# PC_Memory.net
KiCad netlist of a schematic drawn in Altium Designer
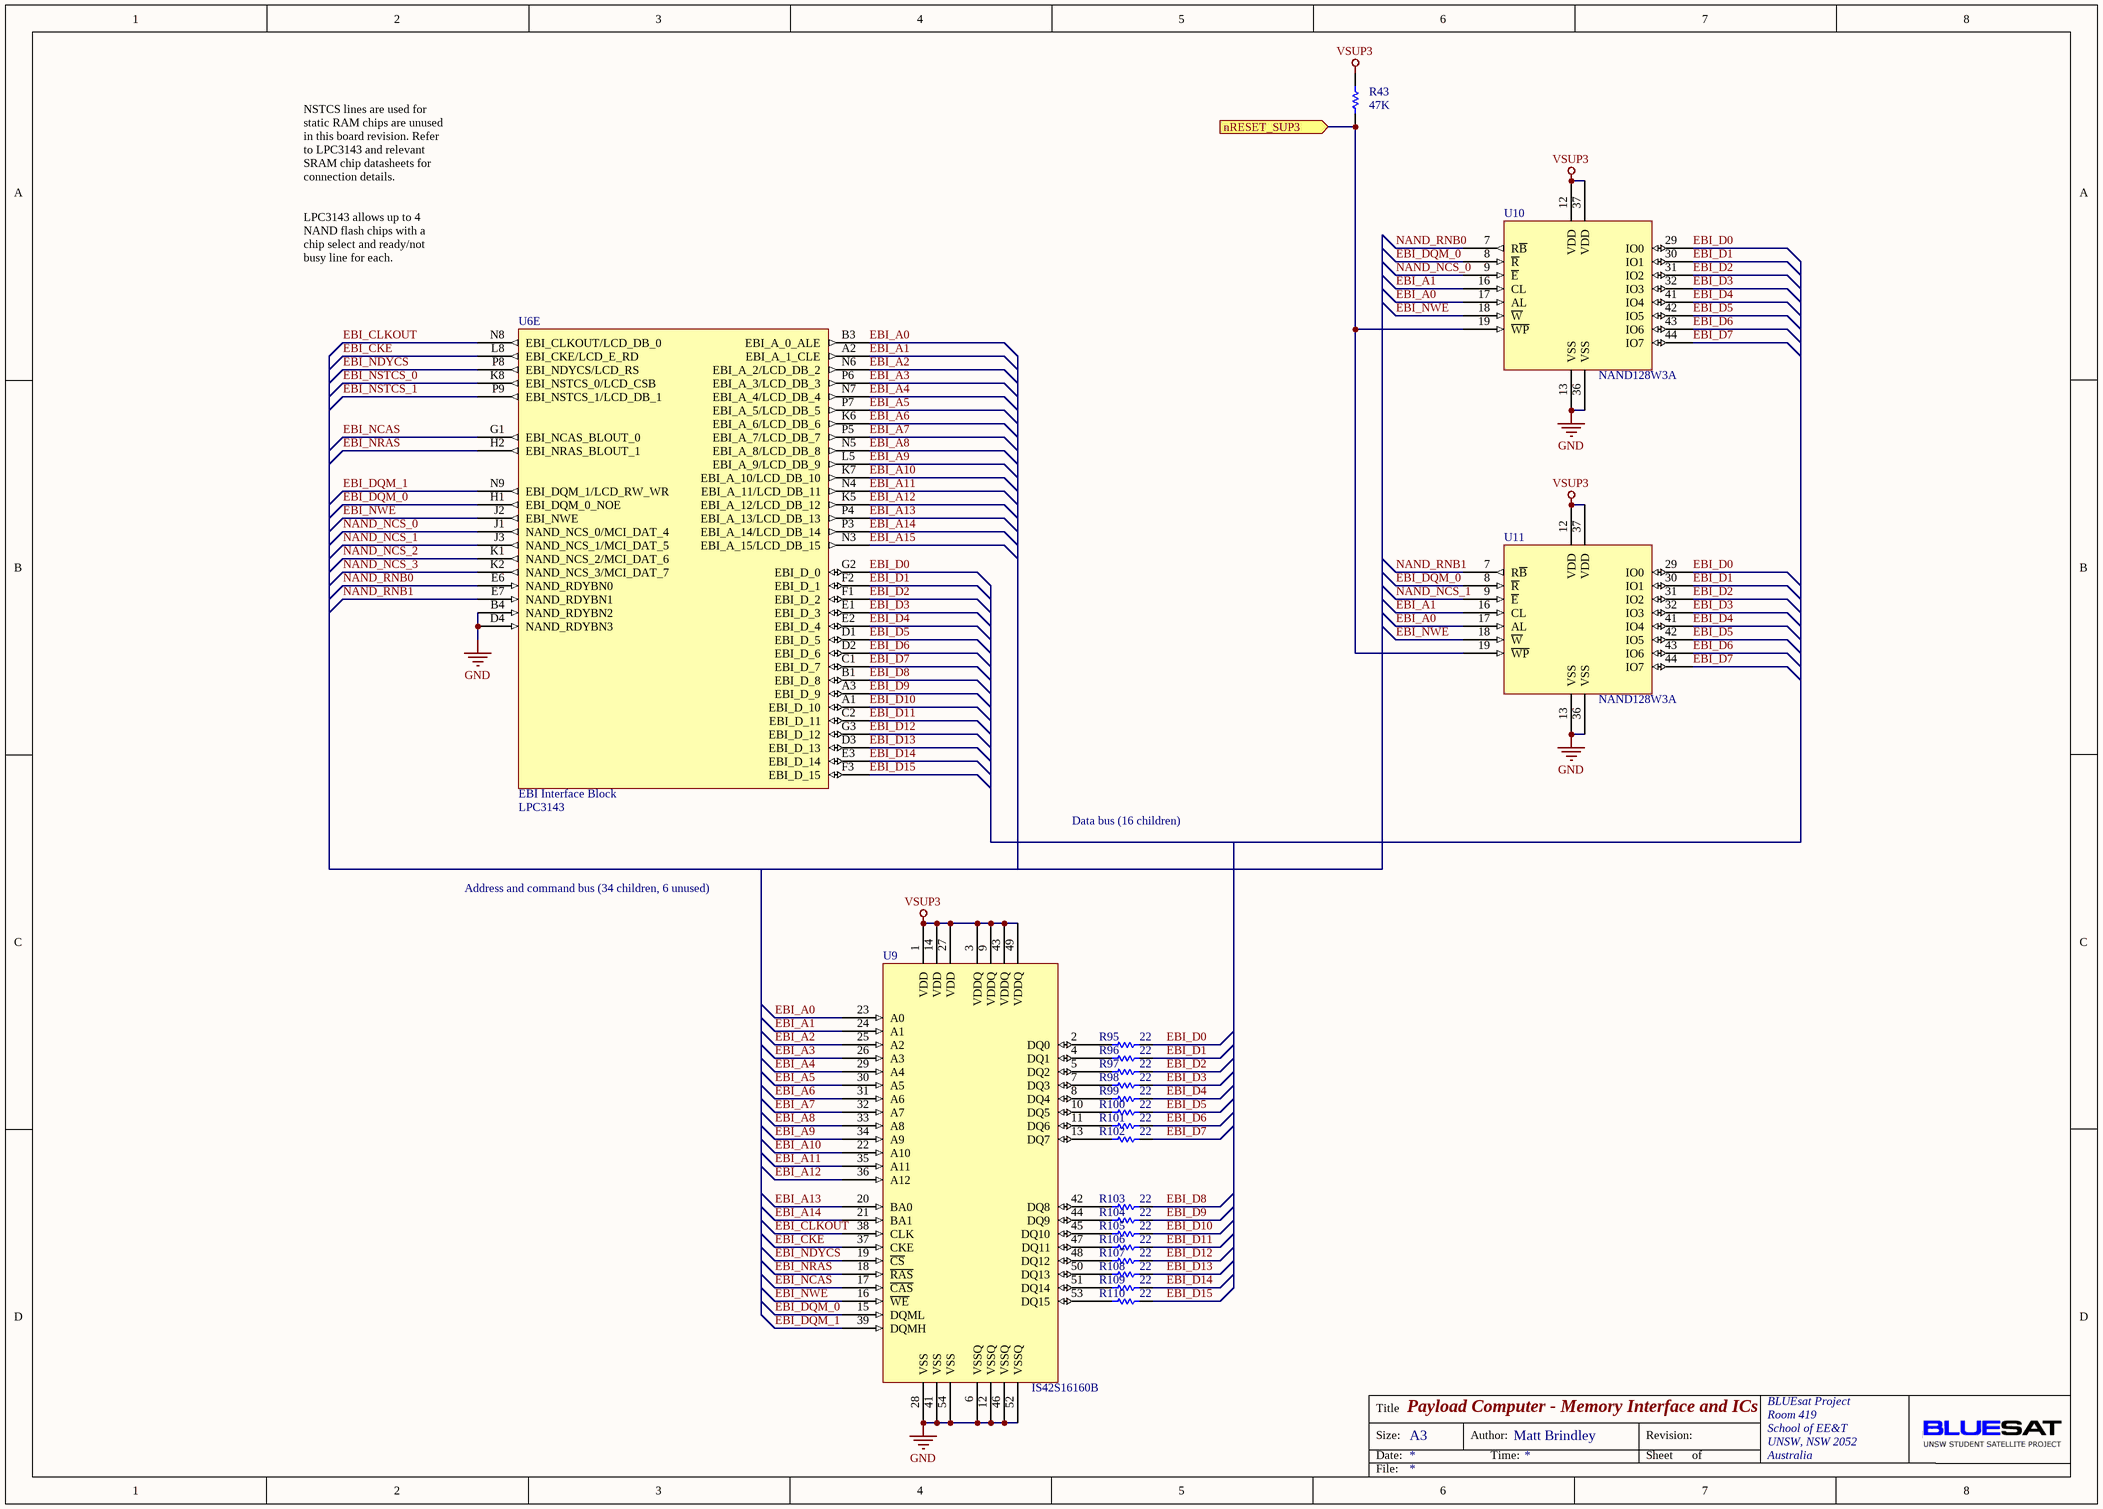
[diagram p0: PC_Memory.SchDoc]

(export (version "E")
  (design (tool "Eeschema 10.0.6"))
  (components
    (comp (ref "R43")
      (value "47K")
      (footprint "6-0805_L")
      (description "Semiconductor Resistor")
      (fields (field (name "Comment") "Res Semi") (field (name "PUBLISHER") "Altium Limited"))
      (libsource (lib "Miscellaneous Devices") (part "Res Semi"))
    )
    (comp (ref "R95")
      (value "22")
      (footprint "6-0805_L")
      (description "Semiconductor Resistor")
      (fields (field (name "Comment") "Res Semi") (field (name "PUBLISHER") "Altium Limited"))
      (libsource (lib "Miscellaneous Devices") (part "Res Semi"))
    )
    (comp (ref "R96")
      (value "22")
      (footprint "6-0805_L")
      (description "Semiconductor Resistor")
      (fields (field (name "Comment") "Res Semi") (field (name "PUBLISHER") "Altium Limited"))
      (libsource (lib "Miscellaneous Devices") (part "Res Semi"))
    )
    (comp (ref "R97")
      (value "22")
      (footprint "6-0805_L")
      (description "Semiconductor Resistor")
      (fields (field (name "Comment") "Res Semi") (field (name "PUBLISHER") "Altium Limited"))
      (libsource (lib "Miscellaneous Devices") (part "Res Semi"))
    )
    (comp (ref "R98")
      (value "22")
      (footprint "6-0805_L")
      (description "Semiconductor Resistor")
      (fields (field (name "Comment") "Res Semi") (field (name "PUBLISHER") "Altium Limited"))
      (libsource (lib "Miscellaneous Devices") (part "Res Semi"))
    )
    (comp (ref "R99")
      (value "22")
      (footprint "6-0805_L")
      (description "Semiconductor Resistor")
      (fields (field (name "Comment") "Res Semi") (field (name "PUBLISHER") "Altium Limited"))
      (libsource (lib "Miscellaneous Devices") (part "Res Semi"))
    )
    (comp (ref "R100")
      (value "22")
      (footprint "6-0805_L")
      (description "Semiconductor Resistor")
      (fields (field (name "Comment") "Res Semi") (field (name "PUBLISHER") "Altium Limited"))
      (libsource (lib "Miscellaneous Devices") (part "Res Semi"))
    )
    (comp (ref "R101")
      (value "22")
      (footprint "6-0805_L")
      (description "Semiconductor Resistor")
      (fields (field (name "Comment") "Res Semi") (field (name "PUBLISHER") "Altium Limited"))
      (libsource (lib "Miscellaneous Devices") (part "Res Semi"))
    )
    (comp (ref "R102")
      (value "22")
      (footprint "6-0805_L")
      (description "Semiconductor Resistor")
      (fields (field (name "Comment") "Res Semi") (field (name "PUBLISHER") "Altium Limited"))
      (libsource (lib "Miscellaneous Devices") (part "Res Semi"))
    )
    (comp (ref "R103")
      (value "22")
      (footprint "6-0805_L")
      (description "Semiconductor Resistor")
      (fields (field (name "Comment") "Res Semi") (field (name "PUBLISHER") "Altium Limited"))
      (libsource (lib "Miscellaneous Devices") (part "Res Semi"))
    )
    (comp (ref "R104")
      (value "22")
      (footprint "6-0805_L")
      (description "Semiconductor Resistor")
      (fields (field (name "Comment") "Res Semi") (field (name "PUBLISHER") "Altium Limited"))
      (libsource (lib "Miscellaneous Devices") (part "Res Semi"))
    )
    (comp (ref "R105")
      (value "22")
      (footprint "6-0805_L")
      (description "Semiconductor Resistor")
      (fields (field (name "Comment") "Res Semi") (field (name "PUBLISHER") "Altium Limited"))
      (libsource (lib "Miscellaneous Devices") (part "Res Semi"))
    )
    (comp (ref "R106")
      (value "22")
      (footprint "6-0805_L")
      (description "Semiconductor Resistor")
      (fields (field (name "Comment") "Res Semi") (field (name "PUBLISHER") "Altium Limited"))
      (libsource (lib "Miscellaneous Devices") (part "Res Semi"))
    )
    (comp (ref "R107")
      (value "22")
      (footprint "6-0805_L")
      (description "Semiconductor Resistor")
      (fields (field (name "Comment") "Res Semi") (field (name "PUBLISHER") "Altium Limited"))
      (libsource (lib "Miscellaneous Devices") (part "Res Semi"))
    )
    (comp (ref "R108")
      (value "22")
      (footprint "6-0805_L")
      (description "Semiconductor Resistor")
      (fields (field (name "Comment") "Res Semi") (field (name "PUBLISHER") "Altium Limited"))
      (libsource (lib "Miscellaneous Devices") (part "Res Semi"))
    )
    (comp (ref "R109")
      (value "22")
      (footprint "6-0805_L")
      (description "Semiconductor Resistor")
      (fields (field (name "Comment") "Res Semi") (field (name "PUBLISHER") "Altium Limited"))
      (libsource (lib "Miscellaneous Devices") (part "Res Semi"))
    )
    (comp (ref "R110")
      (value "22")
      (footprint "6-0805_L")
      (description "Semiconductor Resistor")
      (fields (field (name "Comment") "Res Semi") (field (name "PUBLISHER") "Altium Limited"))
      (libsource (lib "Miscellaneous Devices") (part "Res Semi"))
    )
    (comp (ref "U6")
      (value "LPC3143")
      (footprint "PC_Footprints:BGA180C80P14X14_1200X1200X120")
      (description "NXP ARM9 based microcontroller")
      (fields (field (name "PUBLISHER") "BLUEsat Project"))
      (libsource (lib "PC_Components") (part "LPC3143"))
    )
    (comp (ref "U9")
      (value "IS42S16160B")
      (footprint "TSOP80P1180X120-54M")
      (description "16Mb x 16 (256Mb) Parallel Interface SDRAM")
      (fields (field (name "PUBLISHER") "Altium Limited"))
      (libsource (lib "PC_Components") (part "IS42S16160B"))
    )
    (comp (ref "U10")
      (value "NAND128W3A")
      (footprint "TSSOP50P2000X120-48M")
      (description "128Mb 8b wide NAND Flash")
      (fields (field (name "PUBLISHER") "Altium Limited"))
      (libsource (lib "PC_Components") (part "NAND128W3A"))
    )
    (comp (ref "U11")
      (value "NAND128W3A")
      (footprint "TSSOP50P2000X120-48M")
      (description "128Mb 8b wide NAND Flash")
      (fields (field (name "PUBLISHER") "Altium Limited"))
      (libsource (lib "PC_Components") (part "NAND128W3A"))
    )
  )
  (nets
    (net (code "1") (name "/EBI_A0") (class "Default")
      (node (ref "U10") (pin "17") (pinfunction "AL_17") (pintype "input"))
      (node (ref "U11") (pin "17") (pinfunction "AL_17") (pintype "input"))
      (node (ref "U6") (pin "B3") (pinfunction "EBI_A_0_ALE_B3") (pintype "output"))
      (node (ref "U9") (pin "23") (pinfunction "A0_23") (pintype "input"))
    )
    (net (code "2") (name "/EBI_A1") (class "Default")
      (node (ref "U10") (pin "16") (pinfunction "CL_16") (pintype "input"))
      (node (ref "U11") (pin "16") (pinfunction "CL_16") (pintype "input"))
      (node (ref "U6") (pin "A2") (pinfunction "EBI_A_1_CLE_A2") (pintype "output"))
      (node (ref "U9") (pin "24") (pinfunction "A1_24") (pintype "input"))
    )
    (net (code "3") (name "/EBI_A2") (class "Default")
      (node (ref "U6") (pin "N6") (pinfunction "EBI_A_2/LCD_DB_2_N6") (pintype "output"))
      (node (ref "U9") (pin "25") (pinfunction "A2_25") (pintype "input"))
    )
    (net (code "4") (name "/EBI_A3") (class "Default")
      (node (ref "U6") (pin "P6") (pinfunction "EBI_A_3/LCD_DB_3_P6") (pintype "output"))
      (node (ref "U9") (pin "26") (pinfunction "A3_26") (pintype "input"))
    )
    (net (code "5") (name "/EBI_A4") (class "Default")
      (node (ref "U6") (pin "N7") (pinfunction "EBI_A_4/LCD_DB_4_N7") (pintype "output"))
      (node (ref "U9") (pin "29") (pinfunction "A4_29") (pintype "input"))
    )
    (net (code "6") (name "/EBI_A5") (class "Default")
      (node (ref "U6") (pin "P7") (pinfunction "EBI_A_5/LCD_DB_5_P7") (pintype "output"))
      (node (ref "U9") (pin "30") (pinfunction "A5_30") (pintype "input"))
    )
    (net (code "7") (name "/EBI_A6") (class "Default")
      (node (ref "U6") (pin "K6") (pinfunction "EBI_A_6/LCD_DB_6_K6") (pintype "output"))
      (node (ref "U9") (pin "31") (pinfunction "A6_31") (pintype "input"))
    )
    (net (code "8") (name "/EBI_A7") (class "Default")
      (node (ref "U6") (pin "P5") (pinfunction "EBI_A_7/LCD_DB_7_P5") (pintype "output"))
      (node (ref "U9") (pin "32") (pinfunction "A7_32") (pintype "input"))
    )
    (net (code "9") (name "/EBI_A8") (class "Default")
      (node (ref "U6") (pin "N5") (pinfunction "EBI_A_8/LCD_DB_8_N5") (pintype "output"))
      (node (ref "U9") (pin "33") (pinfunction "A8_33") (pintype "input"))
    )
    (net (code "10") (name "/EBI_A9") (class "Default")
      (node (ref "U6") (pin "L5") (pinfunction "EBI_A_9/LCD_DB_9_L5") (pintype "output"))
      (node (ref "U9") (pin "34") (pinfunction "A9_34") (pintype "input"))
    )
    (net (code "11") (name "/EBI_A10") (class "Default")
      (node (ref "U6") (pin "K7") (pinfunction "EBI_A_10/LCD_DB_10_K7") (pintype "output"))
      (node (ref "U9") (pin "22") (pinfunction "A10_22") (pintype "input"))
    )
    (net (code "12") (name "/EBI_A11") (class "Default")
      (node (ref "U6") (pin "N4") (pinfunction "EBI_A_11/LCD_DB_11_N4") (pintype "output"))
      (node (ref "U9") (pin "35") (pinfunction "A11_35") (pintype "input"))
    )
    (net (code "13") (name "/EBI_A12") (class "Default")
      (node (ref "U6") (pin "K5") (pinfunction "EBI_A_12/LCD_DB_12_K5") (pintype "output"))
      (node (ref "U9") (pin "36") (pinfunction "A12_36") (pintype "input"))
    )
    (net (code "14") (name "/EBI_A13") (class "Default")
      (node (ref "U6") (pin "P4") (pinfunction "EBI_A_13/LCD_DB_13_P4") (pintype "output"))
      (node (ref "U9") (pin "20") (pinfunction "BA0_20") (pintype "input"))
    )
    (net (code "15") (name "/EBI_A14") (class "Default")
      (node (ref "U6") (pin "P3") (pinfunction "EBI_A_14/LCD_DB_14_P3") (pintype "output"))
      (node (ref "U9") (pin "21") (pinfunction "BA1_21") (pintype "input"))
    )
    (net (code "16") (name "/EBI_A15") (class "Default")
      (node (ref "U6") (pin "N3") (pinfunction "EBI_A_15/LCD_DB_15_N3") (pintype "output"))
    )
    (net (code "17") (name "/EBI_CKE") (class "Default")
      (node (ref "U6") (pin "L8") (pinfunction "EBI_CKE/LCD_E_RD_L8") (pintype "output"))
      (node (ref "U9") (pin "37") (pinfunction "CKE_37") (pintype "input"))
    )
    (net (code "18") (name "/EBI_CLKOUT") (class "Default")
      (node (ref "U6") (pin "N8") (pinfunction "EBI_CLKOUT/LCD_DB_0_N8") (pintype "output"))
      (node (ref "U9") (pin "38") (pinfunction "CLK_38") (pintype "input"))
    )
    (net (code "19") (name "/EBI_D0") (class "Default")
      (node (ref "R95") (pin "2") (pinfunction "2_2") (pintype "passive"))
      (node (ref "U10") (pin "29") (pinfunction "IO0_29") (pintype "bidirectional"))
      (node (ref "U11") (pin "29") (pinfunction "IO0_29") (pintype "bidirectional"))
      (node (ref "U6") (pin "G2") (pinfunction "EBI_D_0_G2") (pintype "bidirectional"))
    )
    (net (code "20") (name "/EBI_D1") (class "Default")
      (node (ref "R96") (pin "2") (pinfunction "2_2") (pintype "passive"))
      (node (ref "U10") (pin "30") (pinfunction "IO1_30") (pintype "bidirectional"))
      (node (ref "U11") (pin "30") (pinfunction "IO1_30") (pintype "bidirectional"))
      (node (ref "U6") (pin "F2") (pinfunction "EBI_D_1_F2") (pintype "bidirectional"))
    )
    (net (code "21") (name "/EBI_D2") (class "Default")
      (node (ref "R97") (pin "2") (pinfunction "2_2") (pintype "passive"))
      (node (ref "U10") (pin "31") (pinfunction "IO2_31") (pintype "bidirectional"))
      (node (ref "U11") (pin "31") (pinfunction "IO2_31") (pintype "bidirectional"))
      (node (ref "U6") (pin "F1") (pinfunction "EBI_D_2_F1") (pintype "bidirectional"))
    )
    (net (code "22") (name "/EBI_D3") (class "Default")
      (node (ref "R98") (pin "2") (pinfunction "2_2") (pintype "passive"))
      (node (ref "U10") (pin "32") (pinfunction "IO3_32") (pintype "bidirectional"))
      (node (ref "U11") (pin "32") (pinfunction "IO3_32") (pintype "bidirectional"))
      (node (ref "U6") (pin "E1") (pinfunction "EBI_D_3_E1") (pintype "bidirectional"))
    )
    (net (code "23") (name "/EBI_D4") (class "Default")
      (node (ref "R99") (pin "2") (pinfunction "2_2") (pintype "passive"))
      (node (ref "U10") (pin "41") (pinfunction "IO4_41") (pintype "bidirectional"))
      (node (ref "U11") (pin "41") (pinfunction "IO4_41") (pintype "bidirectional"))
      (node (ref "U6") (pin "E2") (pinfunction "EBI_D_4_E2") (pintype "bidirectional"))
    )
    (net (code "24") (name "/EBI_D5") (class "Default")
      (node (ref "R100") (pin "2") (pinfunction "2_2") (pintype "passive"))
      (node (ref "U10") (pin "42") (pinfunction "IO5_42") (pintype "bidirectional"))
      (node (ref "U11") (pin "42") (pinfunction "IO5_42") (pintype "bidirectional"))
      (node (ref "U6") (pin "D1") (pinfunction "EBI_D_5_D1") (pintype "bidirectional"))
    )
    (net (code "25") (name "/EBI_D6") (class "Default")
      (node (ref "R101") (pin "2") (pinfunction "2_2") (pintype "passive"))
      (node (ref "U10") (pin "43") (pinfunction "IO6_43") (pintype "bidirectional"))
      (node (ref "U11") (pin "43") (pinfunction "IO6_43") (pintype "bidirectional"))
      (node (ref "U6") (pin "D2") (pinfunction "EBI_D_6_D2") (pintype "bidirectional"))
    )
    (net (code "26") (name "/EBI_D7") (class "Default")
      (node (ref "R102") (pin "2") (pinfunction "2_2") (pintype "passive"))
      (node (ref "U10") (pin "44") (pinfunction "IO7_44") (pintype "bidirectional"))
      (node (ref "U11") (pin "44") (pinfunction "IO7_44") (pintype "bidirectional"))
      (node (ref "U6") (pin "C1") (pinfunction "EBI_D_7_C1") (pintype "bidirectional"))
    )
    (net (code "27") (name "/EBI_D8") (class "Default")
      (node (ref "R103") (pin "2") (pinfunction "2_2") (pintype "passive"))
      (node (ref "U6") (pin "B1") (pinfunction "EBI_D_8_B1") (pintype "bidirectional"))
    )
    (net (code "28") (name "/EBI_D9") (class "Default")
      (node (ref "R104") (pin "2") (pinfunction "2_2") (pintype "passive"))
      (node (ref "U6") (pin "A3") (pinfunction "EBI_D_9_A3") (pintype "bidirectional"))
    )
    (net (code "29") (name "/EBI_D10") (class "Default")
      (node (ref "R105") (pin "2") (pinfunction "2_2") (pintype "passive"))
      (node (ref "U6") (pin "A1") (pinfunction "EBI_D_10_A1") (pintype "bidirectional"))
    )
    (net (code "30") (name "/EBI_D11") (class "Default")
      (node (ref "R106") (pin "2") (pinfunction "2_2") (pintype "passive"))
      (node (ref "U6") (pin "C2") (pinfunction "EBI_D_11_C2") (pintype "bidirectional"))
    )
    (net (code "31") (name "/EBI_D12") (class "Default")
      (node (ref "R107") (pin "2") (pinfunction "2_2") (pintype "passive"))
      (node (ref "U6") (pin "G3") (pinfunction "EBI_D_12_G3") (pintype "bidirectional"))
    )
    (net (code "32") (name "/EBI_D13") (class "Default")
      (node (ref "R108") (pin "2") (pinfunction "2_2") (pintype "passive"))
      (node (ref "U6") (pin "D3") (pinfunction "EBI_D_13_D3") (pintype "bidirectional"))
    )
    (net (code "33") (name "/EBI_D14") (class "Default")
      (node (ref "R109") (pin "2") (pinfunction "2_2") (pintype "passive"))
      (node (ref "U6") (pin "E3") (pinfunction "EBI_D_14_E3") (pintype "bidirectional"))
    )
    (net (code "34") (name "/EBI_D15") (class "Default")
      (node (ref "R110") (pin "2") (pinfunction "2_2") (pintype "passive"))
      (node (ref "U6") (pin "F3") (pinfunction "EBI_D_15_F3") (pintype "bidirectional"))
    )
    (net (code "35") (name "/EBI_DQM_0") (class "Default")
      (node (ref "U10") (pin "8") (pinfunction "~{R}_8") (pintype "input"))
      (node (ref "U11") (pin "8") (pinfunction "~{R}_8") (pintype "input"))
      (node (ref "U6") (pin "H1") (pinfunction "EBI_DQM_0_NOE_H1") (pintype "output"))
      (node (ref "U9") (pin "15") (pinfunction "DQML_15") (pintype "input"))
    )
    (net (code "36") (name "/EBI_DQM_1") (class "Default")
      (node (ref "U6") (pin "N9") (pinfunction "EBI_DQM_1/LCD_RW_WR_N9") (pintype "output"))
      (node (ref "U9") (pin "39") (pinfunction "DQMH_39") (pintype "input"))
    )
    (net (code "37") (name "/EBI_NCAS") (class "Default")
      (node (ref "U6") (pin "G1") (pinfunction "EBI_NCAS_BLOUT_0_G1") (pintype "output"))
      (node (ref "U9") (pin "17") (pinfunction "~{CAS}_17") (pintype "input"))
    )
    (net (code "38") (name "/EBI_NDYCS") (class "Default")
      (node (ref "U6") (pin "P8") (pinfunction "EBI_NDYCS/LCD_RS_P8") (pintype "output"))
      (node (ref "U9") (pin "19") (pinfunction "~{CS}_19") (pintype "input"))
    )
    (net (code "39") (name "/EBI_NRAS") (class "Default")
      (node (ref "U6") (pin "H2") (pinfunction "EBI_NRAS_BLOUT_1_H2") (pintype "output"))
      (node (ref "U9") (pin "18") (pinfunction "~{RAS}_18") (pintype "input"))
    )
    (net (code "40") (name "/EBI_NSTCS_0") (class "Default")
      (node (ref "U6") (pin "K8") (pinfunction "EBI_NSTCS_0/LCD_CSB_K8") (pintype "output"))
    )
    (net (code "41") (name "/EBI_NSTCS_1") (class "Default")
      (node (ref "U6") (pin "P9") (pinfunction "EBI_NSTCS_1/LCD_DB_1_P9") (pintype "output"))
    )
    (net (code "42") (name "/EBI_NWE") (class "Default")
      (node (ref "U10") (pin "18") (pinfunction "~{W}_18") (pintype "input"))
      (node (ref "U11") (pin "18") (pinfunction "~{W}_18") (pintype "input"))
      (node (ref "U6") (pin "J2") (pinfunction "EBI_NWE_J2") (pintype "output"))
      (node (ref "U9") (pin "16") (pinfunction "~{WE}_16") (pintype "input"))
    )
    (net (code "43") (name "/NAND_NCS_0") (class "Default")
      (node (ref "U10") (pin "9") (pinfunction "~{E}_9") (pintype "input"))
      (node (ref "U6") (pin "J1") (pinfunction "NAND_NCS_0/MCI_DAT_4_J1") (pintype "output"))
    )
    (net (code "44") (name "/NAND_NCS_1") (class "Default")
      (node (ref "U11") (pin "9") (pinfunction "~{E}_9") (pintype "input"))
      (node (ref "U6") (pin "J3") (pinfunction "NAND_NCS_1/MCI_DAT_5_J3") (pintype "output"))
    )
    (net (code "45") (name "/NAND_NCS_2") (class "Default")
      (node (ref "U6") (pin "K1") (pinfunction "NAND_NCS_2/MCI_DAT_6_K1") (pintype "output"))
    )
    (net (code "46") (name "/NAND_NCS_3") (class "Default")
      (node (ref "U6") (pin "K2") (pinfunction "NAND_NCS_3/MCI_DAT_7_K2") (pintype "output"))
    )
    (net (code "47") (name "/NAND_RNB0") (class "Default")
      (node (ref "U10") (pin "7") (pinfunction "R~{B}_7") (pintype "output"))
      (node (ref "U6") (pin "E6") (pinfunction "NAND_RDYBN0_E6") (pintype "input"))
    )
    (net (code "48") (name "/NAND_RNB1") (class "Default")
      (node (ref "U11") (pin "7") (pinfunction "R~{B}_7") (pintype "output"))
      (node (ref "U6") (pin "E7") (pinfunction "NAND_RDYBN1_E7") (pintype "input"))
    )
    (net (code "49") (name "/nRESET_SUP3") (class "Default")
      (node (ref "R43") (pin "1") (pinfunction "1_1") (pintype "passive"))
      (node (ref "U10") (pin "19") (pinfunction "~{WP}_19") (pintype "input"))
      (node (ref "U11") (pin "19") (pinfunction "~{WP}_19") (pintype "input"))
    )
    (net (code "50") (name "GND") (class "Default")
      (node (ref "U10") (pin "13") (pinfunction "VSS_13") (pintype "power_in"))
      (node (ref "U10") (pin "36") (pinfunction "VSS_36") (pintype "power_in"))
      (node (ref "U11") (pin "13") (pinfunction "VSS_13") (pintype "power_in"))
      (node (ref "U11") (pin "36") (pinfunction "VSS_36") (pintype "power_in"))
      (node (ref "U6") (pin "B4") (pinfunction "NAND_RDYBN2_B4") (pintype "input"))
      (node (ref "U6") (pin "D4") (pinfunction "NAND_RDYBN3_D4") (pintype "input"))
      (node (ref "U9") (pin "12") (pinfunction "VSSQ_12") (pintype "power_in"))
      (node (ref "U9") (pin "28") (pinfunction "VSS_28") (pintype "power_in"))
      (node (ref "U9") (pin "41") (pinfunction "VSS_41") (pintype "power_in"))
      (node (ref "U9") (pin "46") (pinfunction "VSSQ_46") (pintype "power_in"))
      (node (ref "U9") (pin "52") (pinfunction "VSSQ_52") (pintype "power_in"))
      (node (ref "U9") (pin "54") (pinfunction "VSS_54") (pintype "power_in"))
      (node (ref "U9") (pin "6") (pinfunction "VSSQ_6") (pintype "power_in"))
    )
    (net (code "51") (name "Net-(U9-DQ0)") (class "Default")
      (node (ref "R95") (pin "1") (pinfunction "1_1") (pintype "passive"))
      (node (ref "U9") (pin "2") (pinfunction "DQ0_2") (pintype "bidirectional"))
    )
    (net (code "52") (name "Net-(U9-DQ1)") (class "Default")
      (node (ref "R96") (pin "1") (pinfunction "1_1") (pintype "passive"))
      (node (ref "U9") (pin "4") (pinfunction "DQ1_4") (pintype "bidirectional"))
    )
    (net (code "53") (name "Net-(U9-DQ2)") (class "Default")
      (node (ref "R97") (pin "1") (pinfunction "1_1") (pintype "passive"))
      (node (ref "U9") (pin "5") (pinfunction "DQ2_5") (pintype "bidirectional"))
    )
    (net (code "54") (name "Net-(U9-DQ3)") (class "Default")
      (node (ref "R98") (pin "1") (pinfunction "1_1") (pintype "passive"))
      (node (ref "U9") (pin "7") (pinfunction "DQ3_7") (pintype "bidirectional"))
    )
    (net (code "55") (name "Net-(U9-DQ4)") (class "Default")
      (node (ref "R99") (pin "1") (pinfunction "1_1") (pintype "passive"))
      (node (ref "U9") (pin "8") (pinfunction "DQ4_8") (pintype "bidirectional"))
    )
    (net (code "56") (name "Net-(U9-DQ5)") (class "Default")
      (node (ref "R100") (pin "1") (pinfunction "1_1") (pintype "passive"))
      (node (ref "U9") (pin "10") (pinfunction "DQ5_10") (pintype "bidirectional"))
    )
    (net (code "57") (name "Net-(U9-DQ6)") (class "Default")
      (node (ref "R101") (pin "1") (pinfunction "1_1") (pintype "passive"))
      (node (ref "U9") (pin "11") (pinfunction "DQ6_11") (pintype "bidirectional"))
    )
    (net (code "58") (name "Net-(U9-DQ7)") (class "Default")
      (node (ref "R102") (pin "1") (pinfunction "1_1") (pintype "passive"))
      (node (ref "U9") (pin "13") (pinfunction "DQ7_13") (pintype "bidirectional"))
    )
    (net (code "59") (name "Net-(U9-DQ8)") (class "Default")
      (node (ref "R103") (pin "1") (pinfunction "1_1") (pintype "passive"))
      (node (ref "U9") (pin "42") (pinfunction "DQ8_42") (pintype "bidirectional"))
    )
    (net (code "60") (name "Net-(U9-DQ9)") (class "Default")
      (node (ref "R104") (pin "1") (pinfunction "1_1") (pintype "passive"))
      (node (ref "U9") (pin "44") (pinfunction "DQ9_44") (pintype "bidirectional"))
    )
    (net (code "61") (name "Net-(U9-DQ10)") (class "Default")
      (node (ref "R105") (pin "1") (pinfunction "1_1") (pintype "passive"))
      (node (ref "U9") (pin "45") (pinfunction "DQ10_45") (pintype "bidirectional"))
    )
    (net (code "62") (name "Net-(U9-DQ11)") (class "Default")
      (node (ref "R106") (pin "1") (pinfunction "1_1") (pintype "passive"))
      (node (ref "U9") (pin "47") (pinfunction "DQ11_47") (pintype "bidirectional"))
    )
    (net (code "63") (name "Net-(U9-DQ12)") (class "Default")
      (node (ref "R107") (pin "1") (pinfunction "1_1") (pintype "passive"))
      (node (ref "U9") (pin "48") (pinfunction "DQ12_48") (pintype "bidirectional"))
    )
    (net (code "64") (name "Net-(U9-DQ13)") (class "Default")
      (node (ref "R108") (pin "1") (pinfunction "1_1") (pintype "passive"))
      (node (ref "U9") (pin "50") (pinfunction "DQ13_50") (pintype "bidirectional"))
    )
    (net (code "65") (name "Net-(U9-DQ14)") (class "Default")
      (node (ref "R109") (pin "1") (pinfunction "1_1") (pintype "passive"))
      (node (ref "U9") (pin "51") (pinfunction "DQ14_51") (pintype "bidirectional"))
    )
    (net (code "66") (name "Net-(U9-DQ15)") (class "Default")
      (node (ref "R110") (pin "1") (pinfunction "1_1") (pintype "passive"))
      (node (ref "U9") (pin "53") (pinfunction "DQ15_53") (pintype "bidirectional"))
    )
    (net (code "67") (name "VSUP3") (class "Default")
      (node (ref "R43") (pin "2") (pinfunction "2_2") (pintype "passive"))
      (node (ref "U10") (pin "12") (pinfunction "VDD_12") (pintype "power_in"))
      (node (ref "U10") (pin "37") (pinfunction "VDD_37") (pintype "power_in"))
      (node (ref "U11") (pin "12") (pinfunction "VDD_12") (pintype "power_in"))
      (node (ref "U11") (pin "37") (pinfunction "VDD_37") (pintype "power_in"))
      (node (ref "U9") (pin "1") (pinfunction "VDD_1") (pintype "power_in"))
      (node (ref "U9") (pin "14") (pinfunction "VDD_14") (pintype "power_in"))
      (node (ref "U9") (pin "27") (pinfunction "VDD_27") (pintype "power_in"))
      (node (ref "U9") (pin "3") (pinfunction "VDDQ_3") (pintype "power_in"))
      (node (ref "U9") (pin "43") (pinfunction "VDDQ_43") (pintype "power_in"))
      (node (ref "U9") (pin "49") (pinfunction "VDDQ_49") (pintype "power_in"))
      (node (ref "U9") (pin "9") (pinfunction "VDDQ_9") (pintype "power_in"))
    )
  )
)
